# tinyPixel_-_rev_A.net
KiCad netlist of a schematic drawn in EAGLE
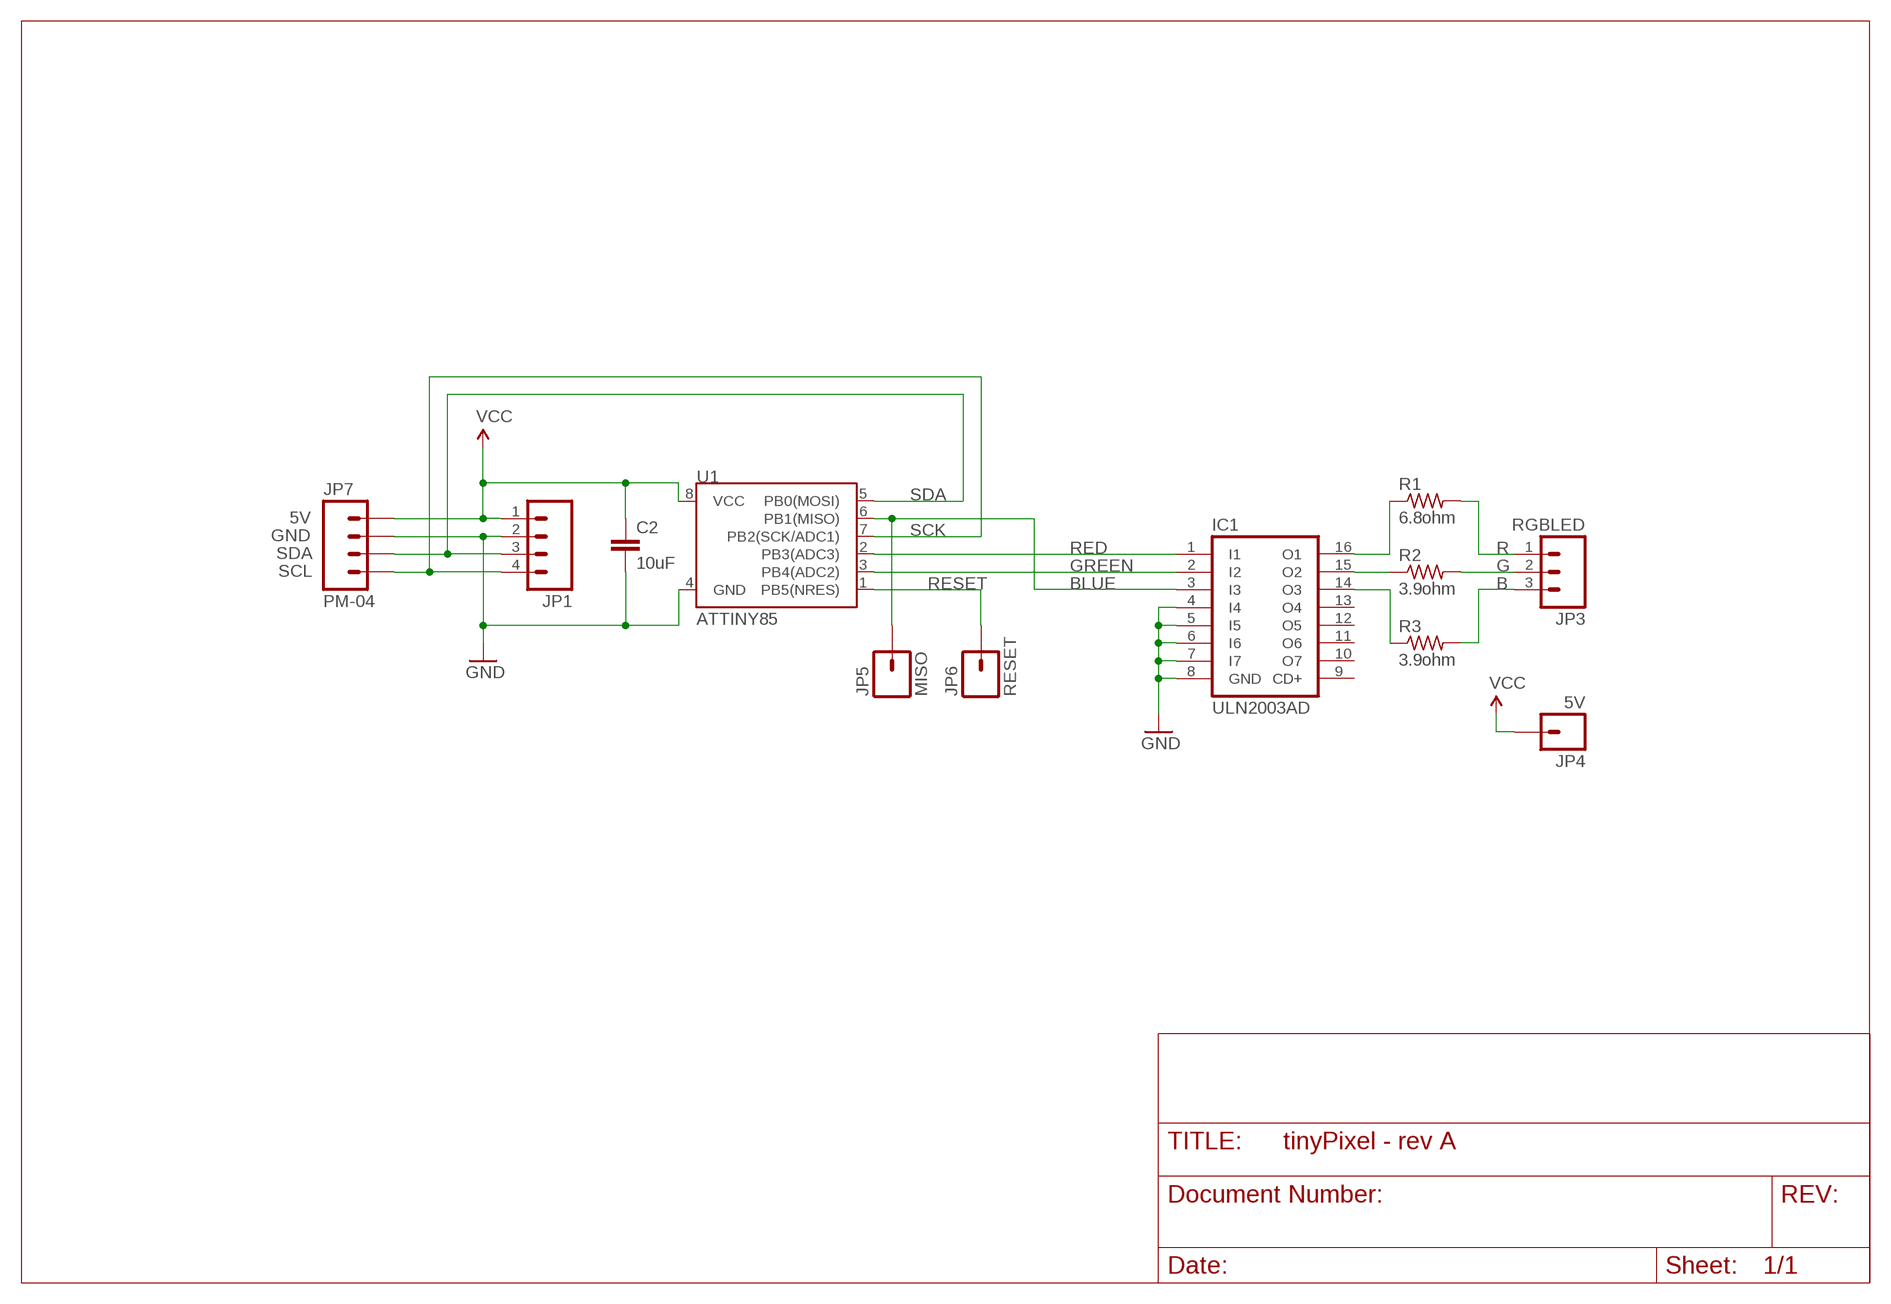
[diagram p0: schematic, sheet 1]

(export (version "E")
  (design (tool "Eeschema 10.0.6"))
  (components
    (comp (ref "C2")
      (value "10uF")
      (footprint "eagle-import:0805")
      (libsource (lib "eagle-import") (part "CAP0805"))
    )
    (comp (ref "IC1")
      (value "ULN2003AD")
      (footprint "eagle-import:SO16")
      (libsource (lib "eagle-import") (part "ULN2003AD"))
    )
    (comp (ref "JP1")
      (value "M04PTH")
      (footprint "eagle-import:1X04")
      (libsource (lib "eagle-import") (part "M04PTH"))
    )
    (comp (ref "JP3")
      (value "RGBLED")
      (footprint "eagle-import:1X03")
      (libsource (lib "eagle-import") (part "M03PTH"))
    )
    (comp (ref "JP4")
      (value "5V")
      (footprint "eagle-import:1X01")
      (libsource (lib "eagle-import") (part "M01PTH"))
    )
    (comp (ref "JP5")
      (value "MISO")
      (footprint "eagle-import:M01-SMD")
      (libsource (lib "eagle-import") (part "M01-SMD"))
    )
    (comp (ref "JP6")
      (value "RESET")
      (footprint "eagle-import:M01-SMD")
      (libsource (lib "eagle-import") (part "M01-SMD"))
    )
    (comp (ref "JP7")
      (value "PM-04")
      (footprint "eagle-import:PM-04")
      (libsource (lib "eagle-import") (part "PM-04"))
    )
    (comp (ref "R1")
      (value "6.8ohm")
      (footprint "eagle-import:0411_12")
      (libsource (lib "eagle-import") (part "R-US_0411/12"))
    )
    (comp (ref "R2")
      (value "3.9ohm")
      (footprint "eagle-import:0411_12")
      (libsource (lib "eagle-import") (part "R-US_0411/12"))
    )
    (comp (ref "R3")
      (value "3.9ohm")
      (footprint "eagle-import:0411_12")
      (libsource (lib "eagle-import") (part "R-US_0411/12"))
    )
    (comp (ref "U1")
      (value "ATTINY85")
      (footprint "eagle-import:SO08-EIAJ")
      (fields (field (name "PROD_ID") "IC-09092"))
      (libsource (lib "eagle-import") (part "ATTINY45TINY85-20-SMT"))
    )
  )
  (nets
    (net (code "1") (name "/B") (class "Default")
      (node (ref "JP3") (pin "3") (pinfunction "3_3") (pintype "passive"))
      (node (ref "R3") (pin "2") (pinfunction "2_2") (pintype "passive"))
    )
    (net (code "2") (name "/BLUE") (class "Default")
      (node (ref "IC1") (pin "3") (pinfunction "I3_3") (pintype "input"))
      (node (ref "JP5") (pin "P$2") (pinfunction "1_P$2") (pintype "passive"))
      (node (ref "U1") (pin "6") (pinfunction "PB1(MISO)_6") (pintype "bidirectional"))
    )
    (net (code "3") (name "/G") (class "Default")
      (node (ref "JP3") (pin "2") (pinfunction "2_2") (pintype "passive"))
      (node (ref "R2") (pin "2") (pinfunction "2_2") (pintype "passive"))
    )
    (net (code "4") (name "/GREEN") (class "Default")
      (node (ref "IC1") (pin "2") (pinfunction "I2_2") (pintype "input"))
      (node (ref "U1") (pin "3") (pinfunction "PB4(ADC2)_3") (pintype "bidirectional"))
    )
    (net (code "5") (name "/R") (class "Default")
      (node (ref "JP3") (pin "1") (pinfunction "1_1") (pintype "passive"))
      (node (ref "R1") (pin "2") (pinfunction "2_2") (pintype "passive"))
    )
    (net (code "6") (name "/RED") (class "Default")
      (node (ref "IC1") (pin "1") (pinfunction "I1_1") (pintype "input"))
      (node (ref "U1") (pin "2") (pinfunction "PB3(ADC3)_2") (pintype "bidirectional"))
    )
    (net (code "7") (name "/RESET") (class "Default")
      (node (ref "JP6") (pin "P$2") (pinfunction "1_P$2") (pintype "passive"))
      (node (ref "U1") (pin "1") (pinfunction "PB5(NRES)_1") (pintype "bidirectional"))
    )
    (net (code "8") (name "/SCK") (class "Default")
      (node (ref "JP1") (pin "4") (pinfunction "4_4") (pintype "passive"))
      (node (ref "JP7") (pin "P$1") (pinfunction "1_P$1") (pintype "passive"))
      (node (ref "U1") (pin "7") (pinfunction "PB2(SCK/ADC1)_7") (pintype "bidirectional"))
    )
    (net (code "9") (name "/SDA") (class "Default")
      (node (ref "JP1") (pin "3") (pinfunction "3_3") (pintype "passive"))
      (node (ref "JP7") (pin "P$2") (pinfunction "2_P$2") (pintype "passive"))
      (node (ref "U1") (pin "5") (pinfunction "PB0(MOSI)_5") (pintype "bidirectional"))
    )
    (net (code "10") (name "GND") (class "Default")
      (node (ref "C2") (pin "2") (pinfunction "2_2") (pintype "passive"))
      (node (ref "IC1") (pin "4") (pinfunction "I4_4") (pintype "input"))
      (node (ref "IC1") (pin "5") (pinfunction "I5_5") (pintype "input"))
      (node (ref "IC1") (pin "6") (pinfunction "I6_6") (pintype "input"))
      (node (ref "IC1") (pin "7") (pinfunction "I7_7") (pintype "input"))
      (node (ref "IC1") (pin "8") (pinfunction "GND_8") (pintype "power_in"))
      (node (ref "JP1") (pin "2") (pinfunction "2_2") (pintype "passive"))
      (node (ref "JP7") (pin "P$3") (pinfunction "3_P$3") (pintype "passive"))
      (node (ref "U1") (pin "4") (pinfunction "GND_4") (pintype "bidirectional"))
    )
    (net (code "11") (name "Net-(IC1-O1)") (class "Default")
      (node (ref "IC1") (pin "16") (pinfunction "O1_16") (pintype "open_collector"))
      (node (ref "R1") (pin "1") (pinfunction "1_1") (pintype "passive"))
    )
    (net (code "12") (name "Net-(IC1-O2)") (class "Default")
      (node (ref "IC1") (pin "15") (pinfunction "O2_15") (pintype "open_collector"))
      (node (ref "R2") (pin "1") (pinfunction "1_1") (pintype "passive"))
    )
    (net (code "13") (name "Net-(IC1-O3)") (class "Default")
      (node (ref "IC1") (pin "14") (pinfunction "O3_14") (pintype "open_collector"))
      (node (ref "R3") (pin "1") (pinfunction "1_1") (pintype "passive"))
    )
    (net (code "14") (name "VCC") (class "Default")
      (node (ref "C2") (pin "1") (pinfunction "1_1") (pintype "passive"))
      (node (ref "JP1") (pin "1") (pinfunction "1_1") (pintype "passive"))
      (node (ref "JP4") (pin "1") (pinfunction "1_1") (pintype "passive"))
      (node (ref "JP7") (pin "P$4") (pinfunction "4_P$4") (pintype "passive"))
      (node (ref "U1") (pin "8") (pinfunction "VCC_8") (pintype "bidirectional"))
    )
    (net (code "15") (name "unconnected-(IC1-CD+-Pad9)") (class "Default")
      (node (ref "IC1") (pin "9") (pinfunction "CD+_9") (pintype "passive"))
    )
    (net (code "16") (name "unconnected-(IC1-O4-Pad13)") (class "Default")
      (node (ref "IC1") (pin "13") (pinfunction "O4_13") (pintype "open_collector"))
    )
    (net (code "17") (name "unconnected-(IC1-O5-Pad12)") (class "Default")
      (node (ref "IC1") (pin "12") (pinfunction "O5_12") (pintype "open_collector"))
    )
    (net (code "18") (name "unconnected-(IC1-O6-Pad11)") (class "Default")
      (node (ref "IC1") (pin "11") (pinfunction "O6_11") (pintype "open_collector"))
    )
    (net (code "19") (name "unconnected-(IC1-O7-Pad10)") (class "Default")
      (node (ref "IC1") (pin "10") (pinfunction "O7_10") (pintype "open_collector"))
    )
  )
)
